# Counter2DigitSF.net
KiCad netlist of a schematic drawn in EAGLE
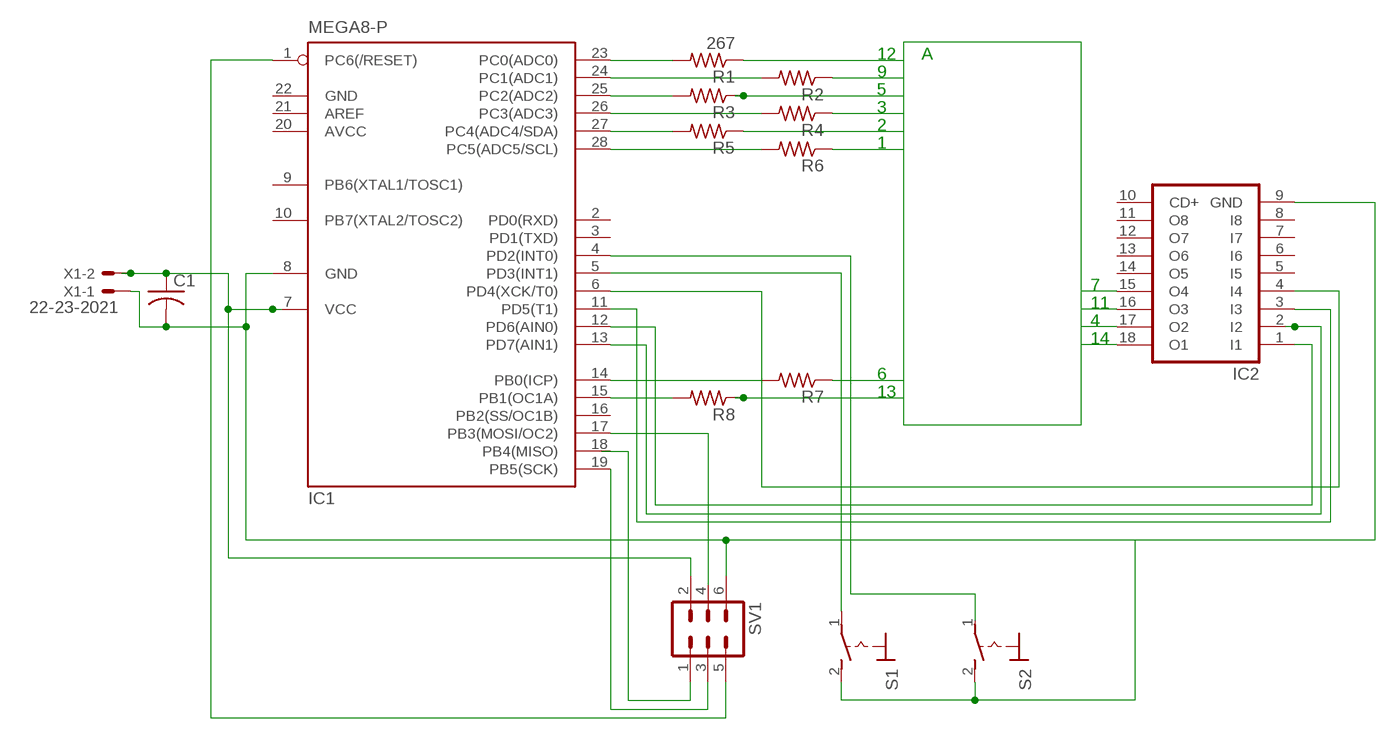
[diagram p0: schematic, sheet 1]

(export (version "E")
  (design (tool "Eeschema 10.0.6"))
  (components
    (comp (ref "C1")
      (value "C-USC0805")
      (footprint "eagle-import:C0805")
      (libsource (lib "eagle-import") (part "C-USC0805"))
    )
    (comp (ref "IC1")
      (value "MEGA8-P")
      (footprint "eagle-import:DIL28-3")
      (libsource (lib "eagle-import") (part "MEGA8-P"))
    )
    (comp (ref "IC2")
      (value "ULN2803A")
      (footprint "eagle-import:DIL18")
      (libsource (lib "eagle-import") (part "ULN2803A"))
    )
    (comp (ref "R1")
      (value "267")
      (footprint "eagle-import:M0805")
      (libsource (lib "eagle-import") (part "R-US_M0805"))
    )
    (comp (ref "R2")
      (value "R-US_M0805")
      (footprint "eagle-import:M0805")
      (libsource (lib "eagle-import") (part "R-US_M0805"))
    )
    (comp (ref "R3")
      (value "R-US_M0805")
      (footprint "eagle-import:M0805")
      (libsource (lib "eagle-import") (part "R-US_M0805"))
    )
    (comp (ref "R4")
      (value "R-US_M0805")
      (footprint "eagle-import:M0805")
      (libsource (lib "eagle-import") (part "R-US_M0805"))
    )
    (comp (ref "R5")
      (value "R-US_M0805")
      (footprint "eagle-import:M0805")
      (libsource (lib "eagle-import") (part "R-US_M0805"))
    )
    (comp (ref "R6")
      (value "R-US_M0805")
      (footprint "eagle-import:M0805")
      (libsource (lib "eagle-import") (part "R-US_M0805"))
    )
    (comp (ref "R7")
      (value "R-US_M0805")
      (footprint "eagle-import:M0805")
      (libsource (lib "eagle-import") (part "R-US_M0805"))
    )
    (comp (ref "R8")
      (value "R-US_M0805")
      (footprint "eagle-import:M0805")
      (libsource (lib "eagle-import") (part "R-US_M0805"))
    )
    (comp (ref "S1")
      (value "MS243")
      (footprint "eagle-import:MS243")
      (libsource (lib "eagle-import") (part "MS243"))
    )
    (comp (ref "S2")
      (value "MS243")
      (footprint "eagle-import:MS243")
      (libsource (lib "eagle-import") (part "MS243"))
    )
    (comp (ref "SV1")
      (value "MA03-2")
      (footprint "eagle-import:MA03-2")
      (libsource (lib "eagle-import") (part "MA03-2"))
    )
    (comp (ref "X1")
      (value "22-23-2021")
      (footprint "eagle-import:22-23-2021")
      (fields (field (name "MF") "MOLEX"))
      (libsource (lib "eagle-import") (part "22-23-2021"))
    )
  )
  (nets
    (net (code "1") (name "/AVCC") (class "Default")
      (node (ref "IC1") (pin "20") (pinfunction "AVCC_20") (pintype "power_in"))
    )
    (net (code "2") (name "/GND") (class "Default")
      (node (ref "IC1") (pin "22") (pinfunction "GND_22") (pintype "power_in"))
    )
    (net (code "3") (name "Net-(IC1-PB0(ICP))") (class "Default")
      (node (ref "IC1") (pin "14") (pinfunction "PB0(ICP)_14") (pintype "bidirectional"))
      (node (ref "R7") (pin "2") (pinfunction "2_2") (pintype "passive"))
    )
    (net (code "4") (name "Net-(IC1-PB1(OC1A))") (class "Default")
      (node (ref "IC1") (pin "15") (pinfunction "PB1(OC1A)_15") (pintype "bidirectional"))
      (node (ref "R8") (pin "2") (pinfunction "2_2") (pintype "passive"))
    )
    (net (code "5") (name "Net-(IC1-PB5(SCK))") (class "Default")
      (node (ref "IC1") (pin "19") (pinfunction "PB5(SCK)_19") (pintype "bidirectional"))
      (node (ref "SV1") (pin "3") (pinfunction "3_3") (pintype "passive"))
    )
    (net (code "6") (name "Net-(IC1-PC0(ADC0))") (class "Default")
      (node (ref "IC1") (pin "23") (pinfunction "PC0(ADC0)_23") (pintype "bidirectional"))
      (node (ref "R1") (pin "2") (pinfunction "2_2") (pintype "passive"))
    )
    (net (code "7") (name "Net-(IC1-PC1(ADC1))") (class "Default")
      (node (ref "IC1") (pin "24") (pinfunction "PC1(ADC1)_24") (pintype "bidirectional"))
      (node (ref "R2") (pin "2") (pinfunction "2_2") (pintype "passive"))
    )
    (net (code "8") (name "Net-(IC1-PC2(ADC2))") (class "Default")
      (node (ref "IC1") (pin "25") (pinfunction "PC2(ADC2)_25") (pintype "bidirectional"))
      (node (ref "R3") (pin "2") (pinfunction "2_2") (pintype "passive"))
    )
    (net (code "9") (name "Net-(IC1-PC3(ADC3))") (class "Default")
      (node (ref "IC1") (pin "26") (pinfunction "PC3(ADC3)_26") (pintype "bidirectional"))
      (node (ref "R4") (pin "2") (pinfunction "2_2") (pintype "passive"))
    )
    (net (code "10") (name "Net-(IC1-PC4(ADC4{slash}SDA))") (class "Default")
      (node (ref "IC1") (pin "27") (pinfunction "PC4(ADC4/SDA)_27") (pintype "bidirectional"))
      (node (ref "R5") (pin "2") (pinfunction "2_2") (pintype "passive"))
    )
    (net (code "11") (name "Net-(IC1-PC5(ADC5{slash}SCL))") (class "Default")
      (node (ref "IC1") (pin "28") (pinfunction "PC5(ADC5/SCL)_28") (pintype "bidirectional"))
      (node (ref "R6") (pin "2") (pinfunction "2_2") (pintype "passive"))
    )
    (net (code "12") (name "Net-(IC1-PC6({slash}RESET))") (class "Default")
      (node (ref "IC1") (pin "1") (pinfunction "PC6(/RESET)_1") (pintype "bidirectional"))
      (node (ref "SV1") (pin "5") (pinfunction "5_5") (pintype "passive"))
    )
    (net (code "13") (name "Net-(IC1-PD3(INT1))") (class "Default")
      (node (ref "IC1") (pin "5") (pinfunction "PD3(INT1)_5") (pintype "bidirectional"))
      (node (ref "S1") (pin "1") (pinfunction "P_1") (pintype "passive"))
    )
    (net (code "14") (name "Net-(IC1-PD4(XCK{slash}T0))") (class "Default")
      (node (ref "IC1") (pin "6") (pinfunction "PD4(XCK/T0)_6") (pintype "bidirectional"))
      (node (ref "IC2") (pin "4") (pinfunction "I4_4") (pintype "input"))
    )
    (net (code "15") (name "Net-(IC1-PD5(T1))") (class "Default")
      (node (ref "IC1") (pin "11") (pinfunction "PD5(T1)_11") (pintype "bidirectional"))
      (node (ref "IC2") (pin "3") (pinfunction "I3_3") (pintype "input"))
    )
    (net (code "16") (name "Net-(IC1-PD6(AIN0))") (class "Default")
      (node (ref "IC1") (pin "12") (pinfunction "PD6(AIN0)_12") (pintype "bidirectional"))
      (node (ref "IC2") (pin "1") (pinfunction "I1_1") (pintype "input"))
    )
    (net (code "17") (name "Net-(IC1-PD7(AIN1))") (class "Default")
      (node (ref "IC1") (pin "13") (pinfunction "PD7(AIN1)_13") (pintype "bidirectional"))
      (node (ref "IC2") (pin "2") (pinfunction "I2_2") (pintype "input"))
    )
    (net (code "18") (name "Net-(IC1-VCC)") (class "Default")
      (node (ref "C1") (pin "1") (pinfunction "1_1") (pintype "passive"))
      (node (ref "IC1") (pin "7") (pinfunction "VCC_7") (pintype "power_in"))
      (node (ref "SV1") (pin "2") (pinfunction "2_2") (pintype "passive"))
      (node (ref "X1") (pin "2") (pinfunction "S_2") (pintype "passive"))
    )
    (net (code "19") (name "Net-(IC2-GND)") (class "Default")
      (node (ref "C1") (pin "2") (pinfunction "2_2") (pintype "passive"))
      (node (ref "IC1") (pin "8") (pinfunction "GND_8") (pintype "power_in"))
      (node (ref "IC2") (pin "9") (pinfunction "GND_9") (pintype "power_in"))
      (node (ref "S1") (pin "2") (pinfunction "S_2") (pintype "passive"))
      (node (ref "S2") (pin "2") (pinfunction "S_2") (pintype "passive"))
      (node (ref "SV1") (pin "6") (pinfunction "6_6") (pintype "passive"))
      (node (ref "X1") (pin "1") (pinfunction "S_1") (pintype "passive"))
    )
    (net (code "20") (name "Net-(IC2-O1)") (class "Default")
      (node (ref "IC2") (pin "15") (pinfunction "O4_15") (pintype "open_collector"))
      (node (ref "IC2") (pin "16") (pinfunction "O3_16") (pintype "open_collector"))
      (node (ref "IC2") (pin "17") (pinfunction "O2_17") (pintype "open_collector"))
      (node (ref "IC2") (pin "18") (pinfunction "O1_18") (pintype "open_collector"))
      (node (ref "R1") (pin "1") (pinfunction "1_1") (pintype "passive"))
      (node (ref "R2") (pin "1") (pinfunction "1_1") (pintype "passive"))
      (node (ref "R3") (pin "1") (pinfunction "1_1") (pintype "passive"))
      (node (ref "R5") (pin "1") (pinfunction "1_1") (pintype "passive"))
      (node (ref "R6") (pin "1") (pinfunction "1_1") (pintype "passive"))
      (node (ref "R7") (pin "1") (pinfunction "1_1") (pintype "passive"))
      (node (ref "R8") (pin "1") (pinfunction "1_1") (pintype "passive"))
    )
    (net (code "21") (name "unconnected-(IC1-AREF-Pad21)") (class "Default")
      (node (ref "IC1") (pin "21") (pinfunction "AREF_21") (pintype "passive"))
    )
    (net (code "22") (name "unconnected-(IC1-PB2(SS{slash}OC1B)-Pad16)") (class "Default")
      (node (ref "IC1") (pin "16") (pinfunction "PB2(SS/OC1B)_16") (pintype "bidirectional"))
    )
    (net (code "23") (name "unconnected-(IC1-PB3(MOSI{slash}OC2)-Pad17)") (class "Default")
      (node (ref "IC1") (pin "17") (pinfunction "PB3(MOSI/OC2)_17") (pintype "bidirectional"))
    )
    (net (code "24") (name "unconnected-(IC1-PB4(MISO)-Pad18)") (class "Default")
      (node (ref "IC1") (pin "18") (pinfunction "PB4(MISO)_18") (pintype "bidirectional"))
    )
    (net (code "25") (name "unconnected-(IC1-PB6(XTAL1{slash}TOSC1)-Pad9)") (class "Default")
      (node (ref "IC1") (pin "9") (pinfunction "PB6(XTAL1/TOSC1)_9") (pintype "bidirectional"))
    )
    (net (code "26") (name "unconnected-(IC1-PB7(XTAL2{slash}TOSC2)-Pad10)") (class "Default")
      (node (ref "IC1") (pin "10") (pinfunction "PB7(XTAL2/TOSC2)_10") (pintype "bidirectional"))
    )
    (net (code "27") (name "unconnected-(IC1-PD0(RXD)-Pad2)") (class "Default")
      (node (ref "IC1") (pin "2") (pinfunction "PD0(RXD)_2") (pintype "bidirectional"))
    )
    (net (code "28") (name "unconnected-(IC1-PD1(TXD)-Pad3)") (class "Default")
      (node (ref "IC1") (pin "3") (pinfunction "PD1(TXD)_3") (pintype "bidirectional"))
    )
    (net (code "29") (name "unconnected-(IC1-PD2(INT0)-Pad4)") (class "Default")
      (node (ref "IC1") (pin "4") (pinfunction "PD2(INT0)_4") (pintype "bidirectional"))
    )
    (net (code "30") (name "unconnected-(IC2-CD+-Pad10)") (class "Default")
      (node (ref "IC2") (pin "10") (pinfunction "CD+_10") (pintype "passive"))
    )
    (net (code "31") (name "unconnected-(IC2-I5-Pad5)") (class "Default")
      (node (ref "IC2") (pin "5") (pinfunction "I5_5") (pintype "input"))
    )
    (net (code "32") (name "unconnected-(IC2-I6-Pad6)") (class "Default")
      (node (ref "IC2") (pin "6") (pinfunction "I6_6") (pintype "input"))
    )
    (net (code "33") (name "unconnected-(IC2-I7-Pad7)") (class "Default")
      (node (ref "IC2") (pin "7") (pinfunction "I7_7") (pintype "input"))
    )
    (net (code "34") (name "unconnected-(IC2-I8-Pad8)") (class "Default")
      (node (ref "IC2") (pin "8") (pinfunction "I8_8") (pintype "input"))
    )
    (net (code "35") (name "unconnected-(IC2-O5-Pad14)") (class "Default")
      (node (ref "IC2") (pin "14") (pinfunction "O5_14") (pintype "open_collector"))
    )
    (net (code "36") (name "unconnected-(IC2-O6-Pad13)") (class "Default")
      (node (ref "IC2") (pin "13") (pinfunction "O6_13") (pintype "open_collector"))
    )
    (net (code "37") (name "unconnected-(IC2-O7-Pad12)") (class "Default")
      (node (ref "IC2") (pin "12") (pinfunction "O7_12") (pintype "open_collector"))
    )
    (net (code "38") (name "unconnected-(IC2-O8-Pad11)") (class "Default")
      (node (ref "IC2") (pin "11") (pinfunction "O8_11") (pintype "open_collector"))
    )
    (net (code "39") (name "unconnected-(R4-Pad1)") (class "Default")
      (node (ref "R4") (pin "1") (pinfunction "1_1") (pintype "passive"))
    )
    (net (code "40") (name "unconnected-(S2-P-Pad1)") (class "Default")
      (node (ref "S2") (pin "1") (pinfunction "P_1") (pintype "passive"))
    )
    (net (code "41") (name "unconnected-(SV1-Pad1)") (class "Default")
      (node (ref "SV1") (pin "1") (pinfunction "1_1") (pintype "passive"))
    )
    (net (code "42") (name "unconnected-(SV1-Pad4)") (class "Default")
      (node (ref "SV1") (pin "4") (pinfunction "4_4") (pintype "passive"))
    )
  )
)
